# 1_5V.net
KiCad netlist of a schematic drawn in Altium Designer
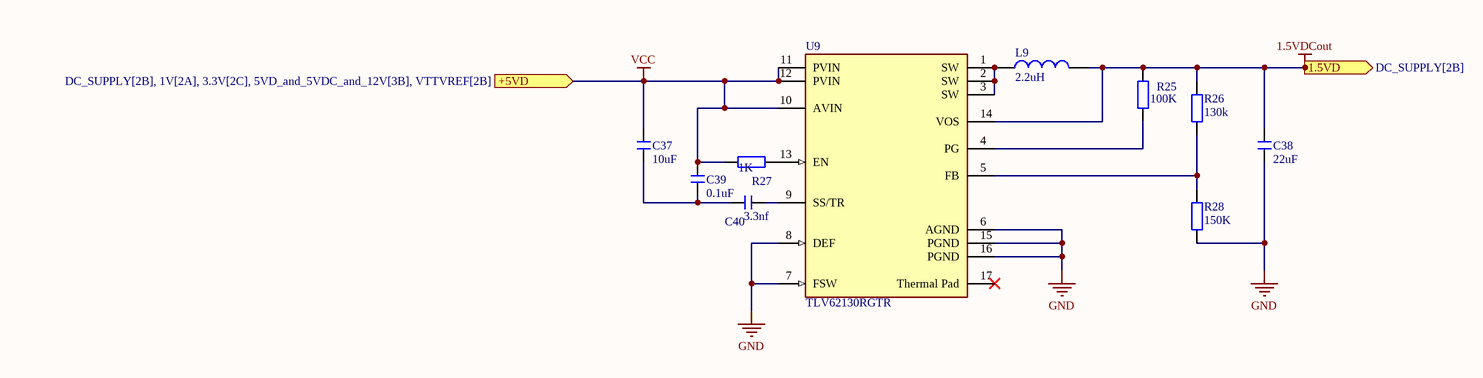
[diagram p0: 1.5V.SchDoc]

(export (version "E")
  (design (tool "Eeschema 10.0.6"))
  (components
    (comp (ref "C37")
      (value "10uF")
      (footprint "C 0805_L")
      (description "贴片电容 10 µF, 25 V, Ceramic, 1210 Standard")
      (libsource (lib "0.1 - 电阻-电容-电感") (part "C"))
    )
    (comp (ref "C38")
      (value "22uF")
      (footprint "C 0805_L")
      (description "贴片电容 22 µF, 6.3 V, Ceramic, 0805 Standard")
      (libsource (lib "0.1 - 电阻-电容-电感") (part "C"))
    )
    (comp (ref "C39")
      (value "0.1uF")
      (footprint "C 0805_L")
      (description "贴片电容 0.1 µF, 25V, Ceramic, 0603")
      (libsource (lib "0.1 - 电阻-电容-电感") (part "C"))
    )
    (comp (ref "C40")
      (value "3.3nf")
      (footprint "C 0805_L")
      (description "贴片电容 3300 pF, 25 V, Ceramic, 0603")
      (libsource (lib "0.1 - 电阻-电容-电感") (part "C"))
    )
    (comp (ref "L9")
      (value "2.2uH")
      (footprint "L 0805")
      (description "小功率贴片电感 2.2 µH, 0.165 × 0.165 in XFL4020-222MEB, Coilcraft")
      (libsource (lib "0.1 - 电阻-电容-电感") (part "L"))
    )
    (comp (ref "R25")
      (value "100K")
      (footprint "R 0805_L")
      (description "贴片电阻 100 kΩ, Chip, 0603, 1/16W, 1%")
      (fields (field (name "版权归属") "来自淘宝 ID：黄晶宝石"))
      (libsource (lib "0.1 - 电阻-电容-电感") (part "R"))
    )
    (comp (ref "R26")
      (value "130k")
      (footprint "R 0805_L")
      (description "贴片电阻")
      (fields (field (name "版权归属") "来自淘宝 ID：黄晶宝石"))
      (libsource (lib "0.1 - 电阻-电容-电感") (part "R"))
    )
    (comp (ref "R27")
      (value "1K")
      (footprint "R 0805_L")
      (description "贴片电阻R1 IMPORTANT, TO PREVENT HV DAMAGE")
      (fields (field (name "版权归属") "来自淘宝 ID：黄晶宝石"))
      (libsource (lib "0.1 - 电阻-电容-电感") (part "R"))
    )
    (comp (ref "R28")
      (value "150K")
      (footprint "R 0805_L")
      (description "贴片电阻")
      (fields (field (name "版权归属") "来自淘宝 ID：黄晶宝石"))
      (libsource (lib "0.1 - 电阻-电容-电感") (part "R"))
    )
    (comp (ref "U9")
      (value "TLV62130RGTR")
      (footprint "FP-RGT0016C-IPC_A")
      (description "IC REG BUCK ADJUSTABLE 3A 16QFN")
      (fields
        (field (name "MANUFACTURER") "Texas Instruments")
        (field (name "OCTOPART") "https://octopart.com/tlv62130rgtr-texas+instruments-21766117")
      )
      (libsource (lib "Components - 23.10.23 - 12.36") (part "CMP-04918-000039-1"))
    )
  )
  (nets
    (net (code "1") (name "1.5VDCout") (class "Default")
      (node (ref "C38") (pin "2") (pinfunction "2_2") (pintype "passive"))
      (node (ref "L9") (pin "2") (pinfunction "2_2") (pintype "passive"))
      (node (ref "R25") (pin "2") (pinfunction "2_2") (pintype "passive"))
      (node (ref "R26") (pin "2") (pinfunction "2_2") (pintype "passive"))
      (node (ref "U9") (pin "14") (pinfunction "VOS_14") (pintype "passive"))
    )
    (net (code "2") (name "GND") (class "Default")
      (node (ref "C38") (pin "1") (pinfunction "1_1") (pintype "passive"))
      (node (ref "R28") (pin "1") (pinfunction "1_1") (pintype "passive"))
      (node (ref "U9") (pin "15") (pinfunction "PGND_15") (pintype "power_in"))
      (node (ref "U9") (pin "16") (pinfunction "PGND_16") (pintype "power_in"))
      (node (ref "U9") (pin "6") (pinfunction "AGND_6") (pintype "power_in"))
      (node (ref "U9") (pin "7") (pinfunction "FSW_7") (pintype "input"))
      (node (ref "U9") (pin "8") (pinfunction "DEF_8") (pintype "input"))
    )
    (net (code "3") (name "Net-(C37-Pad1)") (class "Default")
      (node (ref "C37") (pin "1") (pinfunction "1_1") (pintype "passive"))
      (node (ref "C39") (pin "1") (pinfunction "1_1") (pintype "passive"))
      (node (ref "C40") (pin "1") (pinfunction "1_1") (pintype "passive"))
    )
    (net (code "4") (name "Net-(L9-Pad1)") (class "Default")
      (node (ref "L9") (pin "1") (pinfunction "1_1") (pintype "passive"))
      (node (ref "U9") (pin "1") (pinfunction "SW_1") (pintype "passive"))
      (node (ref "U9") (pin "2") (pinfunction "SW_2") (pintype "passive"))
      (node (ref "U9") (pin "3") (pinfunction "SW_3") (pintype "passive"))
    )
    (net (code "5") (name "Net-(U9-EN)") (class "Default")
      (node (ref "R27") (pin "2") (pinfunction "2_2") (pintype "passive"))
      (node (ref "U9") (pin "13") (pinfunction "EN_13") (pintype "input"))
    )
    (net (code "6") (name "Net-(U9-FB)") (class "Default")
      (node (ref "R26") (pin "1") (pinfunction "1_1") (pintype "passive"))
      (node (ref "R28") (pin "2") (pinfunction "2_2") (pintype "passive"))
      (node (ref "U9") (pin "5") (pinfunction "FB_5") (pintype "passive"))
    )
    (net (code "7") (name "Net-(U9-PG)") (class "Default")
      (node (ref "R25") (pin "1") (pinfunction "1_1") (pintype "passive"))
      (node (ref "U9") (pin "4") (pinfunction "PG_4") (pintype "open_collector"))
    )
    (net (code "8") (name "Net-(U9-SS{slash}TR)") (class "Default")
      (node (ref "C40") (pin "2") (pinfunction "2_2") (pintype "passive"))
      (node (ref "U9") (pin "9") (pinfunction "SS/TR_9") (pintype "passive"))
    )
    (net (code "9") (name "VCC") (class "Default")
      (node (ref "C37") (pin "2") (pinfunction "2_2") (pintype "passive"))
      (node (ref "C39") (pin "2") (pinfunction "2_2") (pintype "passive"))
      (node (ref "R27") (pin "1") (pinfunction "1_1") (pintype "passive"))
      (node (ref "U9") (pin "10") (pinfunction "AVIN_10") (pintype "passive"))
      (node (ref "U9") (pin "11") (pinfunction "PVIN_11") (pintype "passive"))
      (node (ref "U9") (pin "12") (pinfunction "PVIN_12") (pintype "passive"))
    )
    (net (code "10") (name "unconnected-(U9-Thermal_Pad-Pad17)") (class "Default")
      (node (ref "U9") (pin "17") (pinfunction "Thermal_Pad_17") (pintype "power_in+no_connect"))
    )
  )
)
